# pca10040_sheet4_connectors.net
KiCad netlist of a schematic drawn in Altium Designer
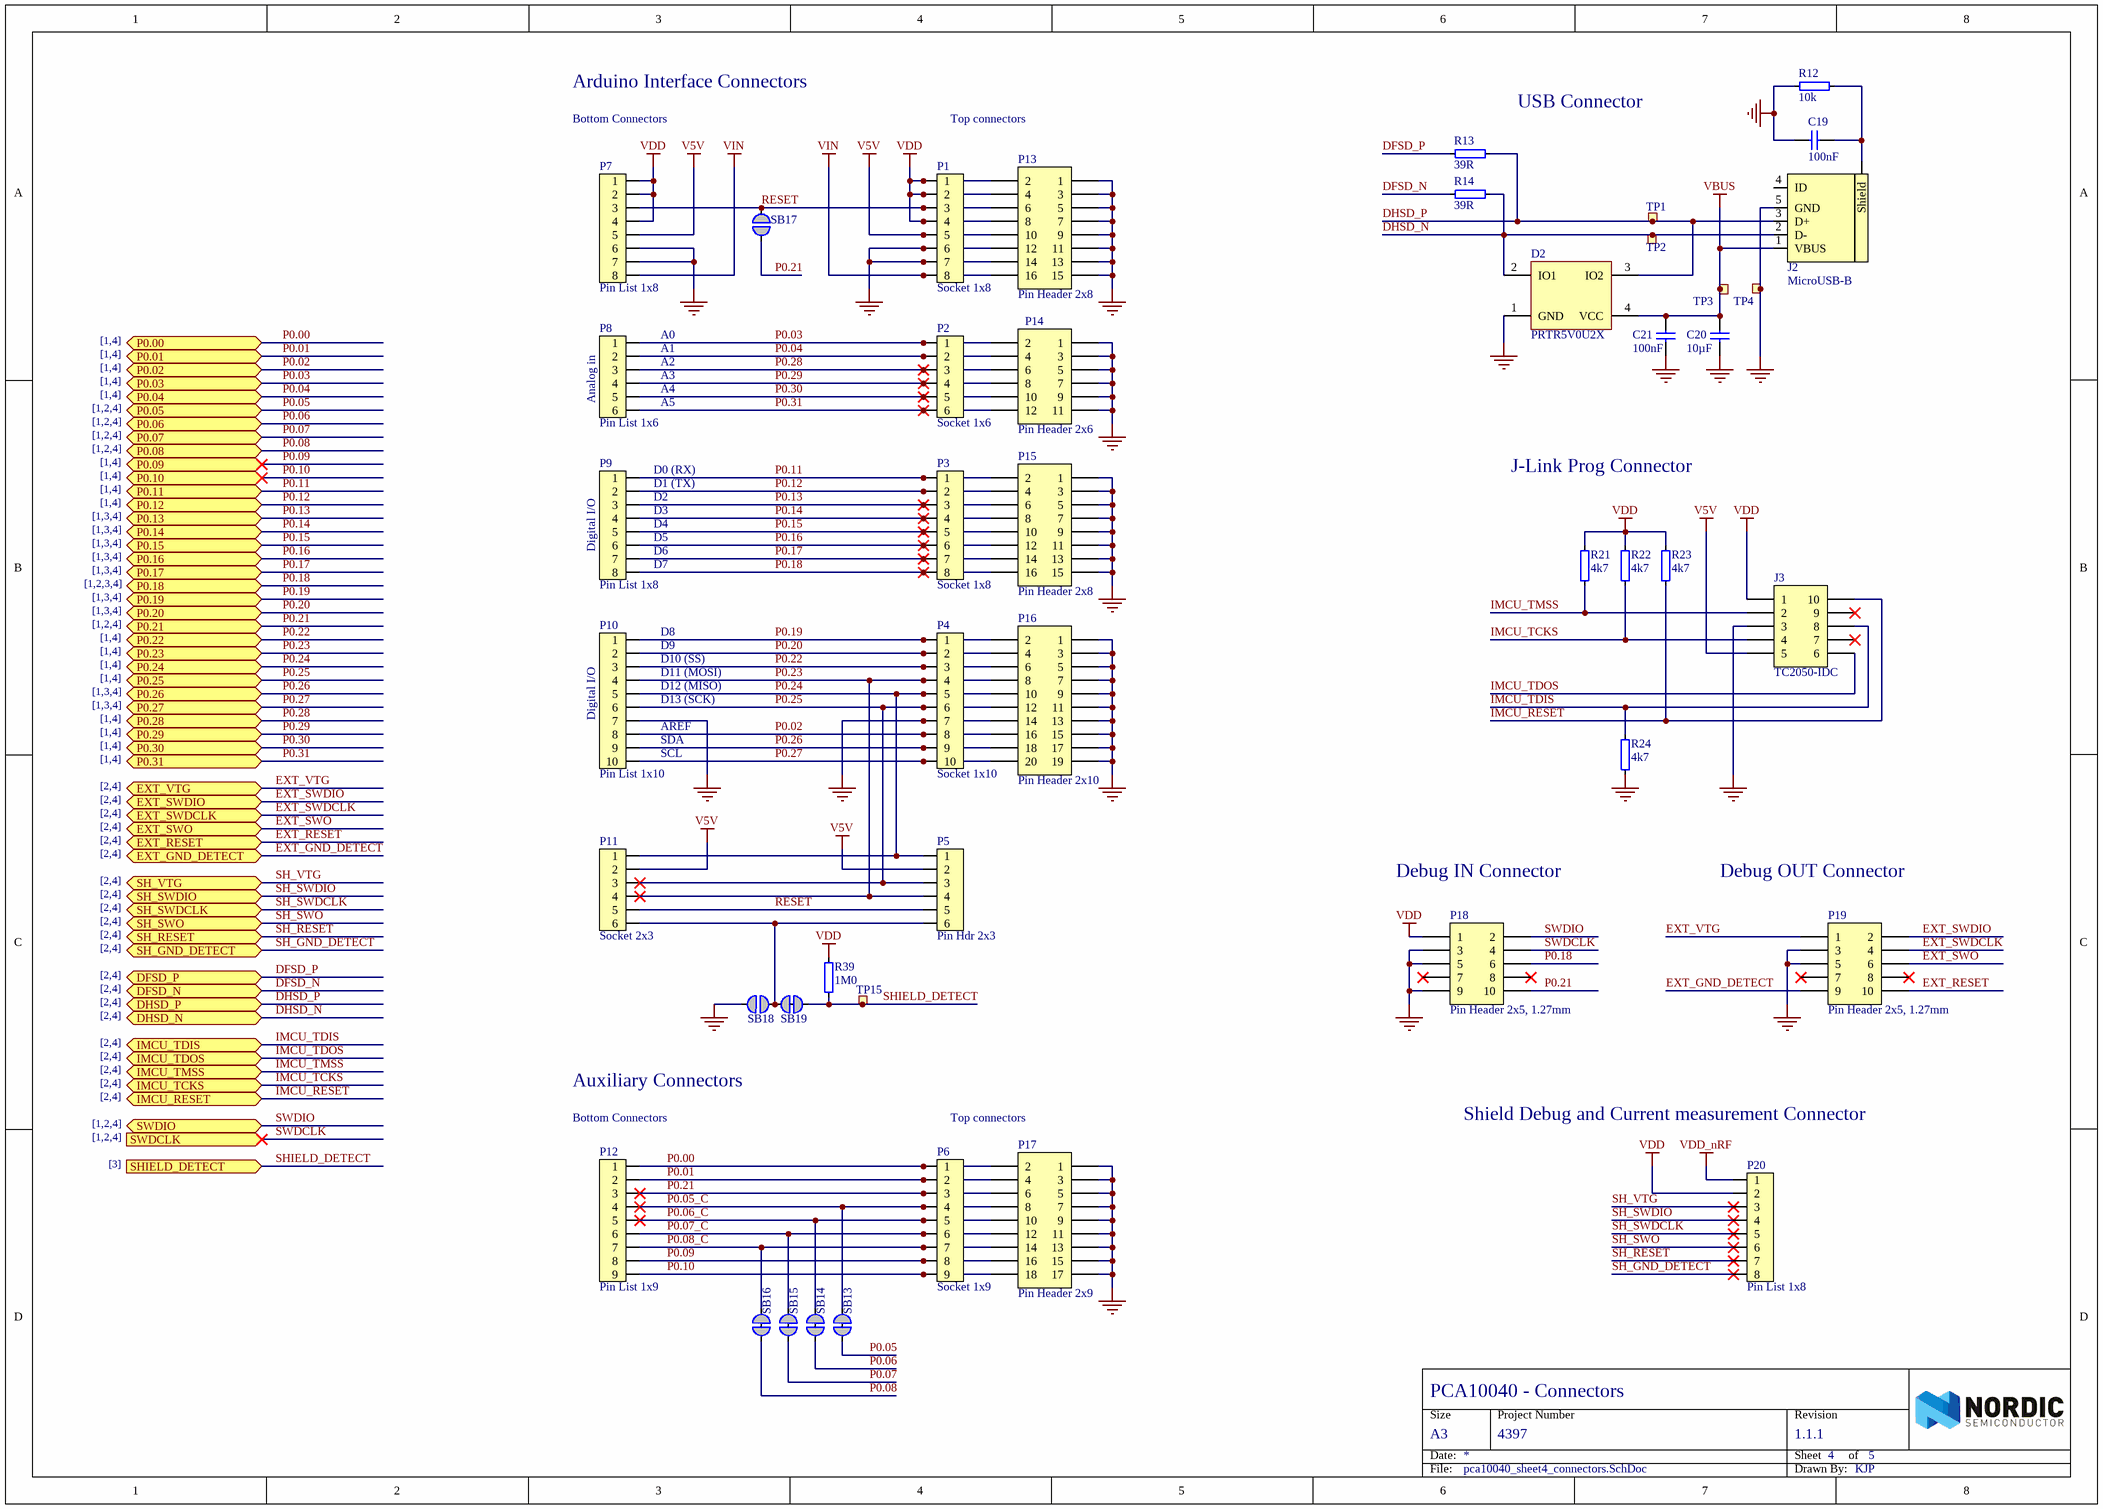
[diagram p0: pca10040_sheet4_connectors.SchDoc]

(export (version "E")
  (design (tool "Eeschema 10.0.6"))
  (components
    (comp (ref "C19")
      (value "100nF")
      (footprint "CAPC1005X04L")
      (description "Capacitor, X7R, ±10%")
      (fields (field (name "PART NUMBER") "C0402-100n") (field (name "PUBLISHER") "Nordic Semiconductor"))
      (libsource (lib "Nordic Passive DB") (part "CAP"))
    )
    (comp (ref "C20")
      (value "10µF")
      (footprint "CAPC1608X06L")
      (description "Capacitor, X5R, ±20%")
      (fields (field (name "PART NUMBER") "C0603-10µ") (field (name "PUBLISHER") "Nordic Semiconductor"))
      (libsource (lib "Nordic Passive DB") (part "CAP"))
    )
    (comp (ref "C21")
      (value "100nF")
      (footprint "CAPC1005X04L")
      (description "Capacitor, X7R, ±10%")
      (fields (field (name "PART NUMBER") "C0402-100n") (field (name "PUBLISHER") "Nordic Semiconductor"))
      (libsource (lib "Nordic Passive DB") (part "CAP"))
    )
    (comp (ref "D2")
      (value "PRTR5V0U2X")
      (footprint "SOT190P230X110-4L")
      (description "Ultra low capacitance double rail-to-rail ESD protection diode")
      (fields
        (field (name "MANUFACTURER") "NXP")
        (field (name "2ND SOURCE PART NUMBER") "152-4157")
        (field (name "PUBLISHER") "Nordic Semiconductor")
      )
      (libsource (lib "Nordic Discrete DB") (part "PRTR5V0U2X"))
    )
    (comp (ref "J2")
      (value "MicroUSB-B")
      (footprint "USB-Micro-B-RA-SMD-PiP")
      (description "MicroUSB-B-SMT")
      (fields
        (field (name "PART NUMBER") "USB-Micro-B-RA-SMD-PiP")
        (field (name "MANUFACTURER") "Allen Creations Corp.")
        (field (name "PUBLISHER") "Nordic Semiconductor")
      )
      (libsource (lib "Nordic Passive DB") (part "MiniUSB-AB-SMT"))
    )
    (comp (ref "J3")
      (value "TC2050-IDC")
      (footprint "TC2050-IDC-NLFP")
      (description "CBL PLUG-OF-NAILS 10-PIN")
      (fields
        (field (name "PART NUMBER") "TC2050-IDC-NLFP")
        (field (name "MANUFACTURER") "Tag-Connect LLC")
        (field (name "PUBLISHER") "Nordic Semiconductor")
      )
      (libsource (lib "Nordic Passive DB") (part "CONN-2x5_var2"))
    )
    (comp (ref "P1")
      (value "Socket 1x8")
      (footprint "SOCKET_1x8_SMD")
      (description "Socket 1x8, 2.54mm (100mil), SMD")
      (fields
        (field (name "PART NUMBER") "Socket 1x8 SMD")
        (field (name "MANUFACTURER") "WCON")
        (field (name "PUBLISHER") "Nordic Semiconductor")
      )
      (libsource (lib "Nordic Passive DB") (part "CONN-8"))
    )
    (comp (ref "P2")
      (value "Socket 1x6")
      (footprint "SOCKET_1x6_SMD")
      (description "Socket 1x6, 2.54mm (100mil), SMD")
      (fields
        (field (name "PART NUMBER") "Socket 1x6 SMD")
        (field (name "MANUFACTURER") "WCON")
        (field (name "PUBLISHER") "Nordic Semiconductor")
      )
      (libsource (lib "Nordic Passive DB") (part "CONN-6"))
    )
    (comp (ref "P3")
      (value "Socket 1x8")
      (footprint "SOCKET_1x8_SMD")
      (description "Socket 1x8, 2.54mm (100mil), SMD")
      (fields
        (field (name "PART NUMBER") "Socket 1x8 SMD")
        (field (name "MANUFACTURER") "WCON")
        (field (name "PUBLISHER") "Nordic Semiconductor")
      )
      (libsource (lib "Nordic Passive DB") (part "CONN-8"))
    )
    (comp (ref "P4")
      (value "Socket 1x10")
      (footprint "SOCKET_1x10_SMD")
      (description "Socket 1x10, 2.54mm (100mil), SMD")
      (fields
        (field (name "PART NUMBER") "Socket 1x10 SMD")
        (field (name "MANUFACTURER") "WCON")
        (field (name "PUBLISHER") "Nordic Semiconductor")
      )
      (libsource (lib "") (part "CONN-10_1"))
    )
    (comp (ref "P5")
      (value "Pin Hdr 2x3")
      (footprint "HDR_2x3-SMD")
      (description "Pin Header 2x3, 2.54mm (100mil) SMD")
      (fields
        (field (name "PART NUMBER") "Pin Header 2x3 SMD")
        (field (name "MANUFACTURER") "WCON")
        (field (name "PUBLISHER") "Nordic Semiconductor")
      )
      (libsource (lib "Nordic Passive DB") (part "CONN-6"))
    )
    (comp (ref "P6")
      (value "Socket 1x9")
      (footprint "SOCKET_1x9_SMD")
      (description "Socket 1x9, 2.54mm (100mil), SMD")
      (fields
        (field (name "PART NUMBER") "Socket 1x9 SMD")
        (field (name "MANUFACTURER") "WCON")
        (field (name "PUBLISHER") "Nordic Semiconductor")
      )
      (libsource (lib "Nordic Passive DB") (part "CONN-9"))
    )
    (comp (ref "P7")
      (value "Pin List 1x8")
      (footprint "LIST_1x8_SMD")
      (description "Pin List 1x8, 2.54mm (100mil), SMD")
      (fields
        (field (name "PART NUMBER") "Pin List 1x8 SMD")
        (field (name "PUBLISHER") "Nordic Semiconductor")
      )
      (libsource (lib "") (part "CONN-8_1"))
    )
    (comp (ref "P8")
      (value "Pin List 1x6")
      (footprint "LIST_1x6_SMD")
      (description "Pin List 1x6, 2.54mm (100mil), SMD")
      (fields
        (field (name "PART NUMBER") "Pin List 1x6 SMD")
        (field (name "PUBLISHER") "Nordic Semiconductor")
      )
      (libsource (lib "") (part "CONN-6_1"))
    )
    (comp (ref "P9")
      (value "Pin List 1x8")
      (footprint "LIST_1x8_SMD")
      (description "Pin List 1x8, 2.54mm (100mil), SMD")
      (fields
        (field (name "PART NUMBER") "Pin List 1x8 SMD")
        (field (name "PUBLISHER") "Nordic Semiconductor")
      )
      (libsource (lib "") (part "CONN-8_1"))
    )
    (comp (ref "P10")
      (value "Pin List 1x10")
      (footprint "LIST_1x10_SMD")
      (description "Pin List 1x10, 2.54mm (100mil), SMD")
      (fields
        (field (name "PART NUMBER") "Pin List 1x10 SMD")
        (field (name "PUBLISHER") "Nordic Semiconductor")
      )
      (libsource (lib "Nordic Passive DB") (part "CONN-10"))
    )
    (comp (ref "P11")
      (value "Socket 2x3")
      (footprint "SOCKET_2x3_SMD-2.54mm-bottom")
      (description "Socket 2x3, 2.54mm (100mil), SMD")
      (fields
        (field (name "PART NUMBER") "Socket 2x3 SMD Bottom")
        (field (name "MANUFACTURER") "Samtec")
        (field (name "PUBLISHER") "Nordic Semiconductor")
      )
      (libsource (lib "") (part "CONN-6_1"))
    )
    (comp (ref "P12")
      (value "Pin List 1x9")
      (footprint "LIST_1x9_SMD")
      (description "Pin List 1x9, 2.54mm (100mil), SMD")
      (fields
        (field (name "PART NUMBER") "Pin List 1x9 SMD")
        (field (name "PUBLISHER") "Nordic Semiconductor")
      )
      (libsource (lib "") (part "CONN-9_1"))
    )
    (comp (ref "P13")
      (value "Pin Header 2x8")
      (footprint "HDR_2x8")
      (description "Pin Header 2x8, 2.54mm (100mil)")
      (fields (field (name "PUBLISHER") "Nordic Semiconductor"))
      (libsource (lib "Nordic Passive DB") (part "CONN-2x8"))
    )
    (comp (ref "P14")
      (value "Pin Header 2x6")
      (footprint "HDR_2x6")
      (description "Pin Header 2x6, 2.54mm (100mil)")
      (fields (field (name "PUBLISHER") "Nordic Semiconductor"))
      (libsource (lib "Nordic Passive DB") (part "CONN-2x6"))
    )
    (comp (ref "P15")
      (value "Pin Header 2x8")
      (footprint "HDR_2x8")
      (description "Pin Header 2x8, 2.54mm (100mil)")
      (fields (field (name "PUBLISHER") "Nordic Semiconductor"))
      (libsource (lib "Nordic Passive DB") (part "CONN-2x8"))
    )
    (comp (ref "P16")
      (value "Pin Header 2x10")
      (footprint "HDR_2x10")
      (description "Pin Header 2x10, 2.54mm (100mil)")
      (fields (field (name "PUBLISHER") "Nordic Semiconductor"))
      (libsource (lib "Nordic Passive DB") (part "CONN-2x10"))
    )
    (comp (ref "P17")
      (value "Pin Header 2x9")
      (footprint "HDR_2x9")
      (description "Pin Header 2x9, 2.54mm (100mil)")
      (fields (field (name "PUBLISHER") "Nordic Semiconductor"))
      (libsource (lib "Nordic Passive DB") (part "CONN-2x9"))
    )
    (comp (ref "P18")
      (value "Pin Header 2x5, 1.27mm")
      (footprint "HDR_2x5-SMD-1.27mm-K")
      (description "Pin Header 2x5, 1.27mm (50mil), SMD, Keying Shroud")
      (fields
        (field (name "PART NUMBER") "Pin Header 2x5 SMD, 1.27mm, KS")
        (field (name "MANUFACTURER") "WCON")
        (field (name "PUBLISHER") "Nordic Semiconductor")
      )
      (libsource (lib "Nordic Passive DB") (part "CONN-2x5"))
    )
    (comp (ref "P19")
      (value "Pin Header 2x5, 1.27mm")
      (footprint "HDR_2x5-SMD-1.27mm-K")
      (description "Pin Header 2x5, 1.27mm (50mil), SMD, Keying Shroud")
      (fields
        (field (name "PART NUMBER") "Pin Header 2x5 SMD, 1.27mm, KS")
        (field (name "MANUFACTURER") "WCON")
        (field (name "PUBLISHER") "Nordic Semiconductor")
      )
      (libsource (lib "Nordic Passive DB") (part "CONN-2x5"))
    )
    (comp (ref "P20")
      (value "Pin List 1x8")
      (footprint "LIST_1x8_SMD")
      (description "Pin List 1x8, 2.54mm (100mil), SMD")
      (fields
        (field (name "PART NUMBER") "Pin List 1x8 SMD")
        (field (name "MANUFACTURER") "WCON")
        (field (name "PUBLISHER") "Nordic Semiconductor")
      )
      (libsource (lib "Nordic Passive DB") (part "CONN-8"))
    )
    (comp (ref "R12")
      (value "10k")
      (footprint "RESC1005X04L")
      (description "Resistor, ±1%, 0.063W")
      (fields (field (name "PART NUMBER") "R0402-10k") (field (name "PUBLISHER") "Nordic Semiconductor"))
      (libsource (lib "Nordic Passive DB") (part "RES_1"))
    )
    (comp (ref "R13")
      (value "39R")
      (footprint "RESC1005X04L")
      (description "Resistor, ±1%, 0.063W")
      (fields (field (name "PART NUMBER") "R0402-39R") (field (name "PUBLISHER") "Nordic Semiconductor"))
      (libsource (lib "Nordic Passive DB") (part "RES_1"))
    )
    (comp (ref "R14")
      (value "39R")
      (footprint "RESC1005X04L")
      (description "Resistor, ±1%, 0.063W")
      (fields (field (name "PART NUMBER") "R0402-39R") (field (name "PUBLISHER") "Nordic Semiconductor"))
      (libsource (lib "Nordic Passive DB") (part "RES_1"))
    )
    (comp (ref "R21")
      (value "4k7")
      (footprint "RESC1005X04L")
      (description "Resistor, ±1%, 0.063W")
      (fields (field (name "PART NUMBER") "R0402-4k7") (field (name "PUBLISHER") "Nordic Semiconductor"))
      (libsource (lib "Nordic Passive DB") (part "RES_1"))
    )
    (comp (ref "R22")
      (value "4k7")
      (footprint "RESC1005X04L")
      (description "Resistor, ±1%, 0.063W")
      (fields (field (name "PART NUMBER") "R0402-4k7") (field (name "PUBLISHER") "Nordic Semiconductor"))
      (libsource (lib "Nordic Passive DB") (part "RES_1"))
    )
    (comp (ref "R23")
      (value "4k7")
      (footprint "RESC1005X04L")
      (description "Resistor, ±1%, 0.063W")
      (fields (field (name "PART NUMBER") "R0402-4k7") (field (name "PUBLISHER") "Nordic Semiconductor"))
      (libsource (lib "Nordic Passive DB") (part "RES_1"))
    )
    (comp (ref "R24")
      (value "4k7")
      (footprint "RESC1005X04L")
      (description "Resistor, ±1%, 0.063W")
      (fields (field (name "PART NUMBER") "R0402-4k7") (field (name "PUBLISHER") "Nordic Semiconductor"))
      (libsource (lib "Nordic Passive DB") (part "RES_1"))
    )
    (comp (ref "R39")
      (value "1M0")
      (footprint "RESC1005X04L")
      (description "Resistor, ±1%, 0.063W")
      (fields (field (name "PART NUMBER") "R0402-1M0") (field (name "PUBLISHER") "Nordic Semiconductor"))
      (libsource (lib "Nordic Passive DB") (part "RES_1"))
    )
    (comp (ref "SB13")
      (value "Solderbridge")
      (footprint "Solderbridge_Shorted")
      (description "Shorted Solderbridge")
      (fields
        (field (name "PART NUMBER") "Solderbridge Shorted")
        (field (name "PUBLISHER") "Nordic Semiconductor")
      )
      (libsource (lib "Nordic Passive DB") (part "SOLDERBRIDGE_SHORTED"))
    )
    (comp (ref "SB14")
      (value "Solderbridge")
      (footprint "Solderbridge_Shorted")
      (description "Shorted Solderbridge")
      (fields
        (field (name "PART NUMBER") "Solderbridge Shorted")
        (field (name "PUBLISHER") "Nordic Semiconductor")
      )
      (libsource (lib "Nordic Passive DB") (part "SOLDERBRIDGE_SHORTED"))
    )
    (comp (ref "SB15")
      (value "Solderbridge")
      (footprint "Solderbridge_Shorted")
      (description "Shorted Solderbridge")
      (fields
        (field (name "PART NUMBER") "Solderbridge Shorted")
        (field (name "PUBLISHER") "Nordic Semiconductor")
      )
      (libsource (lib "Nordic Passive DB") (part "SOLDERBRIDGE_SHORTED"))
    )
    (comp (ref "SB16")
      (value "Solderbridge")
      (footprint "Solderbridge_Shorted")
      (description "Shorted Solderbridge")
      (fields
        (field (name "PART NUMBER") "Solderbridge Shorted")
        (field (name "PUBLISHER") "Nordic Semiconductor")
      )
      (libsource (lib "Nordic Passive DB") (part "SOLDERBRIDGE_SHORTED"))
    )
    (comp (ref "SB17")
      (value "Solderbridge")
      (footprint "Solderbridge")
      (fields (field (name "PUBLISHER") "Nordic Semiconductor"))
      (libsource (lib "Nordic Passive DB") (part "SOLDERBRIDGE"))
    )
    (comp (ref "SB18")
      (value "Solderbridge")
      (footprint "Solderbridge")
      (fields (field (name "PUBLISHER") "Nordic Semiconductor"))
      (libsource (lib "Nordic Passive DB") (part "SOLDERBRIDGE"))
    )
    (comp (ref "SB19")
      (value "Solderbridge")
      (footprint "Solderbridge_Shorted")
      (description "Shorted Solderbridge")
      (fields
        (field (name "PART NUMBER") "Solderbridge Shorted")
        (field (name "PUBLISHER") "Nordic Semiconductor")
      )
      (libsource (lib "Nordic Passive DB") (part "SOLDERBRIDGE_SHORTED"))
    )
    (comp (ref "TP1")
      (value "Ø1.0mm,SMD")
      (footprint "TP_SMD_Ø1.0mm")
      (description "1.0mm circular SMD testpad")
      (fields
        (field (name "PART NUMBER") "TP_SMD_Ø1.0MM")
        (field (name "MANUFACTURER") "Nordic Semiconductor")
        (field (name "PUBLISHER") "Nordic Semiconductor")
      )
      (libsource (lib "Nordic Passive DB") (part "TESTPAD"))
    )
    (comp (ref "TP2")
      (value "Ø1.0mm,SMD")
      (footprint "TP_SMD_Ø1.0mm")
      (description "1.0mm circular SMD testpad")
      (fields
        (field (name "PART NUMBER") "TP_SMD_Ø1.0MM")
        (field (name "MANUFACTURER") "Nordic Semiconductor")
        (field (name "PUBLISHER") "Nordic Semiconductor")
      )
      (libsource (lib "") (part "TESTPAD_1"))
    )
    (comp (ref "TP3")
      (value "Ø1.0mm,SMD")
      (footprint "TP_SMD_Ø1.0mm")
      (description "1.0mm circular SMD testpad")
      (fields
        (field (name "PART NUMBER") "TP_SMD_Ø1.0MM")
        (field (name "MANUFACTURER") "Nordic Semiconductor")
        (field (name "PUBLISHER") "Nordic Semiconductor")
      )
      (libsource (lib "") (part "TESTPAD_2"))
    )
    (comp (ref "TP4")
      (value "Ø1.0mm,SMD")
      (footprint "TP_SMD_Ø1.0mm")
      (description "1.0mm circular SMD testpad")
      (fields
        (field (name "PART NUMBER") "TP_SMD_Ø1.0MM")
        (field (name "MANUFACTURER") "Nordic Semiconductor")
        (field (name "PUBLISHER") "Nordic Semiconductor")
      )
      (libsource (lib "") (part "TESTPAD_3"))
    )
    (comp (ref "TP15")
      (value "Ø1.0mm,SMD")
      (footprint "TP_SMD_Ø1.0mm")
      (description "1.0mm circular SMD testpad")
      (fields
        (field (name "PART NUMBER") "TP_SMD_Ø1.0MM")
        (field (name "MANUFACTURER") "Nordic Semiconductor")
        (field (name "PUBLISHER") "Nordic Semiconductor")
      )
      (libsource (lib "Nordic Passive DB") (part "TESTPAD"))
    )
  )
  (nets
    (net (code "1") (name "/DFSD_N") (class "Default")
      (node (ref "R14") (pin "1") (pinfunction "1_1") (pintype "passive"))
    )
    (net (code "2") (name "/DFSD_P") (class "Default")
      (node (ref "R13") (pin "1") (pinfunction "1_1") (pintype "passive"))
    )
    (net (code "3") (name "/DHSD_N") (class "Default")
      (node (ref "D2") (pin "2") (pinfunction "IO1_2") (pintype "passive"))
      (node (ref "J2") (pin "2") (pinfunction "D-_2") (pintype "passive"))
      (node (ref "R14") (pin "2") (pinfunction "2_2") (pintype "passive"))
      (node (ref "TP2") (pin "1") (pinfunction "1_1") (pintype "passive"))
    )
    (net (code "4") (name "/DHSD_P") (class "Default")
      (node (ref "D2") (pin "3") (pinfunction "IO2_3") (pintype "passive"))
      (node (ref "J2") (pin "3") (pinfunction "D+_3") (pintype "passive"))
      (node (ref "R13") (pin "2") (pinfunction "2_2") (pintype "passive"))
      (node (ref "TP1") (pin "1") (pinfunction "1_1") (pintype "passive"))
    )
    (net (code "5") (name "/EXT_GND_DETECT") (class "Default")
      (node (ref "P19") (pin "9") (pinfunction "9_9") (pintype "passive"))
    )
    (net (code "6") (name "/EXT_RESET") (class "Default")
      (node (ref "P19") (pin "10") (pinfunction "10_10") (pintype "passive"))
    )
    (net (code "7") (name "/EXT_SWDCLK") (class "Default")
      (node (ref "P19") (pin "4") (pinfunction "4_4") (pintype "passive"))
    )
    (net (code "8") (name "/EXT_SWDIO") (class "Default")
      (node (ref "P19") (pin "2") (pinfunction "2_2") (pintype "passive"))
    )
    (net (code "9") (name "/EXT_SWO") (class "Default")
      (node (ref "P19") (pin "6") (pinfunction "6_6") (pintype "passive"))
    )
    (net (code "10") (name "/EXT_VTG") (class "Default")
      (node (ref "P19") (pin "1") (pinfunction "1_1") (pintype "passive"))
    )
    (net (code "11") (name "/IMCU_RESET") (class "Default")
      (node (ref "J3") (pin "10") (pinfunction "10_10") (pintype "passive"))
      (node (ref "R23") (pin "1") (pinfunction "1_1") (pintype "passive"))
    )
    (net (code "12") (name "/IMCU_TCKS") (class "Default")
      (node (ref "J3") (pin "4") (pinfunction "4_4") (pintype "passive"))
      (node (ref "R22") (pin "1") (pinfunction "1_1") (pintype "passive"))
    )
    (net (code "13") (name "/IMCU_TDIS") (class "Default")
      (node (ref "J3") (pin "8") (pinfunction "8_8") (pintype "passive"))
      (node (ref "R24") (pin "1") (pinfunction "1_1") (pintype "passive"))
    )
    (net (code "14") (name "/IMCU_TDOS") (class "Default")
      (node (ref "J3") (pin "6") (pinfunction "6_6") (pintype "passive"))
    )
    (net (code "15") (name "/IMCU_TMSS") (class "Default")
      (node (ref "J3") (pin "2") (pinfunction "2_2") (pintype "passive"))
      (node (ref "R21") (pin "1") (pinfunction "1_1") (pintype "passive"))
    )
    (net (code "16") (name "/P0.00") (class "Default")
      (node (ref "P12") (pin "1") (pinfunction "1_1") (pintype "passive"))
      (node (ref "P17") (pin "2") (pinfunction "2_2") (pintype "passive"))
      (node (ref "P6") (pin "1") (pinfunction "1_1") (pintype "passive"))
    )
    (net (code "17") (name "/P0.01") (class "Default")
      (node (ref "P12") (pin "2") (pinfunction "2_2") (pintype "passive"))
      (node (ref "P17") (pin "4") (pinfunction "4_4") (pintype "passive"))
      (node (ref "P6") (pin "2") (pinfunction "2_2") (pintype "passive"))
    )
    (net (code "18") (name "/P0.02") (class "Default")
      (node (ref "P10") (pin "8") (pinfunction "8_8") (pintype "passive"))
      (node (ref "P16") (pin "16") (pinfunction "16_16") (pintype "passive"))
      (node (ref "P4") (pin "8") (pinfunction "8_8") (pintype "passive"))
    )
    (net (code "19") (name "/P0.03") (class "Default")
      (node (ref "P14") (pin "2") (pinfunction "2_2") (pintype "passive"))
      (node (ref "P2") (pin "1") (pinfunction "1_1") (pintype "passive"))
      (node (ref "P8") (pin "1") (pinfunction "1_1") (pintype "passive"))
    )
    (net (code "20") (name "/P0.04") (class "Default")
      (node (ref "P14") (pin "4") (pinfunction "4_4") (pintype "passive"))
      (node (ref "P2") (pin "2") (pinfunction "2_2") (pintype "passive"))
      (node (ref "P8") (pin "2") (pinfunction "2_2") (pintype "passive"))
    )
    (net (code "21") (name "/P0.05") (class "Default")
      (node (ref "SB13") (pin "2") (pinfunction "1_2") (pintype "passive"))
    )
    (net (code "22") (name "/P0.05_C") (class "Default")
      (node (ref "P12") (pin "4") (pinfunction "4_4") (pintype "power_in"))
      (node (ref "P17") (pin "8") (pinfunction "8_8") (pintype "passive"))
      (node (ref "P6") (pin "4") (pinfunction "4_4") (pintype "power_in"))
      (node (ref "SB13") (pin "1") (pinfunction "0_1") (pintype "passive"))
    )
    (net (code "23") (name "/P0.06") (class "Default")
      (node (ref "SB14") (pin "2") (pinfunction "1_2") (pintype "passive"))
    )
    (net (code "24") (name "/P0.06_C") (class "Default")
      (node (ref "P12") (pin "5") (pinfunction "5_5") (pintype "power_in"))
      (node (ref "P17") (pin "10") (pinfunction "10_10") (pintype "passive"))
      (node (ref "P6") (pin "5") (pinfunction "5_5") (pintype "power_in"))
      (node (ref "SB14") (pin "1") (pinfunction "0_1") (pintype "passive"))
    )
    (net (code "25") (name "/P0.07") (class "Default")
      (node (ref "SB15") (pin "2") (pinfunction "1_2") (pintype "passive"))
    )
    (net (code "26") (name "/P0.07_C") (class "Default")
      (node (ref "P12") (pin "6") (pinfunction "6_6") (pintype "power_in"))
      (node (ref "P17") (pin "12") (pinfunction "12_12") (pintype "passive"))
      (node (ref "P6") (pin "6") (pinfunction "6_6") (pintype "power_in"))
      (node (ref "SB15") (pin "1") (pinfunction "0_1") (pintype "passive"))
    )
    (net (code "27") (name "/P0.08") (class "Default")
      (node (ref "SB16") (pin "2") (pinfunction "1_2") (pintype "passive"))
    )
    (net (code "28") (name "/P0.08_C") (class "Default")
      (node (ref "P12") (pin "7") (pinfunction "7_7") (pintype "power_in"))
      (node (ref "P17") (pin "14") (pinfunction "14_14") (pintype "passive"))
      (node (ref "P6") (pin "7") (pinfunction "7_7") (pintype "power_in"))
      (node (ref "SB16") (pin "1") (pinfunction "0_1") (pintype "passive"))
    )
    (net (code "29") (name "/P0.09") (class "Default")
      (node (ref "P12") (pin "8") (pinfunction "8_8") (pintype "power_in"))
      (node (ref "P17") (pin "16") (pinfunction "16_16") (pintype "passive"))
      (node (ref "P6") (pin "8") (pinfunction "8_8") (pintype "power_in"))
    )
    (net (code "30") (name "/P0.10") (class "Default")
      (node (ref "P12") (pin "9") (pinfunction "9_9") (pintype "power_in"))
      (node (ref "P17") (pin "18") (pinfunction "18_18") (pintype "passive"))
      (node (ref "P6") (pin "9") (pinfunction "9_9") (pintype "power_in"))
    )
    (net (code "31") (name "/P0.11") (class "Default")
      (node (ref "P15") (pin "2") (pinfunction "2_2") (pintype "passive"))
      (node (ref "P3") (pin "1") (pinfunction "1_1") (pintype "passive"))
      (node (ref "P9") (pin "1") (pinfunction "1_1") (pintype "passive"))
    )
    (net (code "32") (name "/P0.12") (class "Default")
      (node (ref "P15") (pin "4") (pinfunction "4_4") (pintype "passive"))
      (node (ref "P3") (pin "2") (pinfunction "2_2") (pintype "passive"))
      (node (ref "P9") (pin "2") (pinfunction "2_2") (pintype "passive"))
    )
    (net (code "33") (name "/P0.13") (class "Default")
      (node (ref "P15") (pin "6") (pinfunction "6_6") (pintype "passive"))
      (node (ref "P3") (pin "3") (pinfunction "3_3") (pintype "passive"))
      (node (ref "P9") (pin "3") (pinfunction "3_3") (pintype "power_in"))
    )
    (net (code "34") (name "/P0.14") (class "Default")
      (node (ref "P15") (pin "8") (pinfunction "8_8") (pintype "passive"))
      (node (ref "P3") (pin "4") (pinfunction "4_4") (pintype "passive"))
      (node (ref "P9") (pin "4") (pinfunction "4_4") (pintype "power_in"))
    )
    (net (code "35") (name "/P0.15") (class "Default")
      (node (ref "P15") (pin "10") (pinfunction "10_10") (pintype "passive"))
      (node (ref "P3") (pin "5") (pinfunction "5_5") (pintype "passive"))
      (node (ref "P9") (pin "5") (pinfunction "5_5") (pintype "power_in"))
    )
    (net (code "36") (name "/P0.16") (class "Default")
      (node (ref "P15") (pin "12") (pinfunction "12_12") (pintype "passive"))
      (node (ref "P3") (pin "6") (pinfunction "6_6") (pintype "passive"))
      (node (ref "P9") (pin "6") (pinfunction "6_6") (pintype "power_in"))
    )
    (net (code "37") (name "/P0.17") (class "Default")
      (node (ref "P15") (pin "14") (pinfunction "14_14") (pintype "passive"))
      (node (ref "P3") (pin "7") (pinfunction "7_7") (pintype "passive"))
      (node (ref "P9") (pin "7") (pinfunction "7_7") (pintype "power_in"))
    )
    (net (code "38") (name "/P0.18") (class "Default")
      (node (ref "P15") (pin "16") (pinfunction "16_16") (pintype "passive"))
      (node (ref "P18") (pin "6") (pinfunction "6_6") (pintype "passive"))
      (node (ref "P3") (pin "8") (pinfunction "8_8") (pintype "passive"))
      (node (ref "P9") (pin "8") (pinfunction "8_8") (pintype "power_in"))
    )
    (net (code "39") (name "/P0.19") (class "Default")
      (node (ref "P10") (pin "1") (pinfunction "1_1") (pintype "passive"))
      (node (ref "P16") (pin "2") (pinfunction "2_2") (pintype "passive"))
      (node (ref "P4") (pin "1") (pinfunction "1_1") (pintype "passive"))
    )
    (net (code "40") (name "/P0.20") (class "Default")
      (node (ref "P10") (pin "2") (pinfunction "2_2") (pintype "passive"))
      (node (ref "P16") (pin "4") (pinfunction "4_4") (pintype "passive"))
      (node (ref "P4") (pin "2") (pinfunction "2_2") (pintype "passive"))
    )
    (net (code "41") (name "/P0.21") (class "Default")
      (node (ref "P12") (pin "3") (pinfunction "3_3") (pintype "power_in"))
      (node (ref "P17") (pin "6") (pinfunction "6_6") (pintype "passive"))
      (node (ref "P18") (pin "10") (pinfunction "10_10") (pintype "passive"))
      (node (ref "P6") (pin "3") (pinfunction "3_3") (pintype "power_in"))
      (node (ref "SB17") (pin "2") (pinfunction "1_2") (pintype "passive"))
    )
    (net (code "42") (name "/P0.22") (class "Default")
      (node (ref "P10") (pin "3") (pinfunction "3_3") (pintype "passive"))
      (node (ref "P16") (pin "6") (pinfunction "6_6") (pintype "passive"))
      (node (ref "P4") (pin "3") (pinfunction "3_3") (pintype "passive"))
    )
    (net (code "43") (name "/P0.23") (class "Default")
      (node (ref "P10") (pin "4") (pinfunction "4_4") (pintype "passive"))
      (node (ref "P11") (pin "4") (pinfunction "4_4") (pintype "power_in"))
      (node (ref "P16") (pin "8") (pinfunction "8_8") (pintype "passive"))
      (node (ref "P4") (pin "4") (pinfunction "4_4") (pintype "passive"))
      (node (ref "P5") (pin "4") (pinfunction "4_4") (pintype "passive"))
    )
    (net (code "44") (name "/P0.24") (class "Default")
      (node (ref "P10") (pin "5") (pinfunction "5_5") (pintype "passive"))
      (node (ref "P11") (pin "1") (pinfunction "1_1") (pintype "passive"))
      (node (ref "P16") (pin "10") (pinfunction "10_10") (pintype "passive"))
      (node (ref "P4") (pin "5") (pinfunction "5_5") (pintype "passive"))
      (node (ref "P5") (pin "1") (pinfunction "1_1") (pintype "passive"))
    )
    (net (code "45") (name "/P0.25") (class "Default")
      (node (ref "P10") (pin "6") (pinfunction "6_6") (pintype "passive"))
      (node (ref "P11") (pin "3") (pinfunction "3_3") (pintype "power_in"))
      (node (ref "P16") (pin "12") (pinfunction "12_12") (pintype "passive"))
      (node (ref "P4") (pin "6") (pinfunction "6_6") (pintype "passive"))
      (node (ref "P5") (pin "3") (pinfunction "3_3") (pintype "passive"))
    )
    (net (code "46") (name "/P0.26") (class "Default")
      (node (ref "P10") (pin "9") (pinfunction "9_9") (pintype "passive"))
      (node (ref "P16") (pin "18") (pinfunction "18_18") (pintype "passive"))
      (node (ref "P4") (pin "9") (pinfunction "9_9") (pintype "passive"))
    )
    (net (code "47") (name "/P0.27") (class "Default")
      (node (ref "P10") (pin "10") (pinfunction "10_10") (pintype "passive"))
      (node (ref "P16") (pin "20") (pinfunction "20_20") (pintype "passive"))
      (node (ref "P4") (pin "10") (pinfunction "10_10") (pintype "passive"))
    )
    (net (code "48") (name "/P0.28") (class "Default")
      (node (ref "P14") (pin "6") (pinfunction "6_6") (pintype "passive"))
      (node (ref "P2") (pin "3") (pinfunction "3_3") (pintype "passive"))
      (node (ref "P8") (pin "3") (pinfunction "3_3") (pintype "power_in"))
    )
    (net (code "49") (name "/P0.29") (class "Default")
      (node (ref "P14") (pin "8") (pinfunction "8_8") (pintype "passive"))
      (node (ref "P2") (pin "4") (pinfunction "4_4") (pintype "passive"))
      (node (ref "P8") (pin "4") (pinfunction "4_4") (pintype "power_in"))
    )
    (net (code "50") (name "/P0.30") (class "Default")
      (node (ref "P14") (pin "10") (pinfunction "10_10") (pintype "passive"))
      (node (ref "P2") (pin "5") (pinfunction "5_5") (pintype "passive"))
      (node (ref "P8") (pin "5") (pinfunction "5_5") (pintype "power_in"))
    )
    (net (code "51") (name "/P0.31") (class "Default")
      (node (ref "P14") (pin "12") (pinfunction "12_12") (pintype "passive"))
      (node (ref "P2") (pin "6") (pinfunction "6_6") (pintype "passive"))
      (node (ref "P8") (pin "6") (pinfunction "6_6") (pintype "power_in"))
    )
    (net (code "52") (name "/RESET") (class "Default")
      (node (ref "P1") (pin "3") (pinfunction "3_3") (pintype "passive"))
      (node (ref "P11") (pin "5") (pinfunction "5_5") (pintype "power_in"))
      (node (ref "P13") (pin "6") (pinfunction "6_6") (pintype "passive"))
      (node (ref "P5") (pin "5") (pinfunction "5_5") (pintype "passive"))
      (node (ref "P7") (pin "3") (pinfunction "3_3") (pintype "power_in"))
      (node (ref "SB17") (pin "1") (pinfunction "0_1") (pintype "passive"))
    )
    (net (code "53") (name "/SHIELD_DETECT") (class "Default")
      (node (ref "R39") (pin "1") (pinfunction "1_1") (pintype "passive"))
      (node (ref "SB19") (pin "2") (pinfunction "1_2") (pintype "passive"))
      (node (ref "TP15") (pin "1") (pinfunction "1_1") (pintype "passive"))
    )
    (net (code "54") (name "/SH_GND_DETECT") (class "Default")
      (node (ref "P20") (pin "8") (pinfunction "8_8") (pintype "passive"))
    )
    (net (code "55") (name "/SH_RESET") (class "Default")
      (node (ref "P20") (pin "7") (pinfunction "7_7") (pintype "passive"))
    )
    (net (code "56") (name "/SH_SWDCLK") (class "Default")
      (node (ref "P20") (pin "5") (pinfunction "5_5") (pintype "passive"))
    )
    (net (code "57") (name "/SH_SWDIO") (class "Default")
      (node (ref "P20") (pin "4") (pinfunction "4_4") (pintype "passive"))
    )
    (net (code "58") (name "/SH_SWO") (class "Default")
      (node (ref "P20") (pin "6") (pinfunction "6_6") (pintype "passive"))
    )
    (net (code "59") (name "/SH_VTG") (class "Default")
      (node (ref "P20") (pin "3") (pinfunction "3_3") (pintype "passive"))
    )
    (net (code "60") (name "/SWDCLK") (class "Default")
      (node (ref "P18") (pin "4") (pinfunction "4_4") (pintype "passive+no_connect"))
    )
    (net (code "61") (name "/SWDIO") (class "Default")
      (node (ref "P18") (pin "2") (pinfunction "2_2") (pintype "passive"))
    )
    (net (code "62") (name "GND") (class "Default")
      (node (ref "C19") (pin "1") (pinfunction "1_1") (pintype "passive"))
      (node (ref "C20") (pin "1") (pinfunction "1_1") (pintype "passive"))
      (node (ref "C21") (pin "1") (pinfunction "1_1") (pintype "passive"))
      (node (ref "D2") (pin "1") (pinfunction "GND_1") (pintype "passive"))
      (node (ref "J2") (pin "5") (pinfunction "GND_5") (pintype "power_in"))
      (node (ref "J3") (pin "3") (pinfunction "3_3") (pintype "passive"))
      (node (ref "P1") (pin "6") (pinfunction "6_6") (pintype "passive"))
      (node (ref "P1") (pin "7") (pinfunction "7_7") (pintype "passive"))
      (node (ref "P10") (pin "7") (pinfunction "7_7") (pintype "passive"))
      (node (ref "P13") (pin "1") (pinfunction "1_1") (pintype "passive"))
      (node (ref "P13") (pin "11") (pinfunction "11_11") (pintype "passive"))
      (node (ref "P13") (pin "12") (pinfunction "12_12") (pintype "passive"))
      (node (ref "P13") (pin "13") (pinfunction "13_13") (pintype "passive"))
      (node (ref "P13") (pin "14") (pinfunction "14_14") (pintype "passive"))
      (node (ref "P13") (pin "15") (pinfunction "15_15") (pintype "passive"))
      (node (ref "P13") (pin "3") (pinfunction "3_3") (pintype "passive"))
      (node (ref "P13") (pin "5") (pinfunction "5_5") (pintype "passive"))
      (node (ref "P13") (pin "7") (pinfunction "7_7") (pintype "passive"))
      (node (ref "P13") (pin "9") (pinfunction "9_9") (pintype "passive"))
      (node (ref "P14") (pin "1") (pinfunction "1_1") (pintype "passive"))
      (node (ref "P14") (pin "11") (pinfunction "11_11") (pintype "passive"))
      (node (ref "P14") (pin "3") (pinfunction "3_3") (pintype "passive"))
      (node (ref "P14") (pin "5") (pinfunction "5_5") (pintype "passive"))
      (node (ref "P14") (pin "7") (pinfunction "7_7") (pintype "passive"))
      (node (ref "P14") (pin "9") (pinfunction "9_9") (pintype "passive"))
      (node (ref "P15") (pin "1") (pinfunction "1_1") (pintype "passive"))
      (node (ref "P15") (pin "11") (pinfunction "11_11") (pintype "passive"))
      (node (ref "P15") (pin "13") (pinfunction "13_13") (pintype "passive"))
      (node (ref "P15") (pin "15") (pinfunction "15_15") (pintype "passive"))
      (node (ref "P15") (pin "3") (pinfunction "3_3") (pintype "passive"))
      (node (ref "P15") (pin "5") (pinfunction "5_5") (pintype "passive"))
      (node (ref "P15") (pin "7") (pinfunction "7_7") (pintype "passive"))
      (node (ref "P15") (pin "9") (pinfunction "9_9") (pintype "passive"))
      (node (ref "P16") (pin "1") (pinfunction "1_1") (pintype "passive"))
      (node (ref "P16") (pin "11") (pinfunction "11_11") (pintype "passive"))
      (node (ref "P16") (pin "13") (pinfunction "13_13") (pintype "passive"))
      (node (ref "P16") (pin "14") (pinfunction "14_14") (pintype "passive"))
      (node (ref "P16") (pin "15") (pinfunction "15_15") (pintype "passive"))
      (node (ref "P16") (pin "17") (pinfunction "17_17") (pintype "passive"))
      (node (ref "P16") (pin "19") (pinfunction "19_19") (pintype "passive"))
      (node (ref "P16") (pin "3") (pinfunction "3_3") (pintype "passive"))
      (node (ref "P16") (pin "5") (pinfunction "5_5") (pintype "passive"))
      (node (ref "P16") (pin "7") (pinfunction "7_7") (pintype "passive"))
      (node (ref "P16") (pin "9") (pinfunction "9_9") (pintype "passive"))
      (node (ref "P17") (pin "1") (pinfunction "1_1") (pintype "passive"))
      (node (ref "P17") (pin "11") (pinfunction "11_11") (pintype "passive"))
      (node (ref "P17") (pin "13") (pinfunction "13_13") (pintype "passive"))
      (node (ref "P17") (pin "15") (pinfunction "15_15") (pintype "passive"))
      (node (ref "P17") (pin "17") (pinfunction "17_17") (pintype "passive"))
      (node (ref "P17") (pin "3") (pinfunction "3_3") (pintype "passive"))
      (node (ref "P17") (pin "5") (pinfunction "5_5") (pintype "passive"))
      (node (ref "P17") (pin "7") (pinfunction "7_7") (pintype "passive"))
      (node (ref "P17") (pin "9") (pinfunction "9_9") (pintype "passive"))
      (node (ref "P18") (pin "3") (pinfunction "3_3") (pintype "passive"))
      (node (ref "P18") (pin "5") (pinfunction "5_5") (pintype "passive"))
      (node (ref "P18") (pin "9") (pinfunction "9_9") (pintype "passive"))
      (node (ref "P19") (pin "3") (pinfunction "3_3") (pintype "passive"))
      (node (ref "P19") (pin "5") (pinfunction "5_5") (pintype "passive"))
      (node (ref "P4") (pin "7") (pinfunction "7_7") (pintype "passive"))
      (node (ref "P7") (pin "6") (pinfunction "6_6") (pintype "power_in"))
      (node (ref "P7") (pin "7") (pinfunction "7_7") (pintype "power_in"))
      (node (ref "R12") (pin "1") (pinfunction "1_1") (pintype "passive"))
      (node (ref "R24") (pin "2") (pinfunction "2_2") (pintype "passive"))
      (node (ref "SB18") (pin "1") (pinfunction "0_1") (pintype "passive"))
      (node (ref "TP4") (pin "1") (pinfunction "1_1") (pintype "passive"))
    )
    (net (code "63") (name "Net-(J2-Shield)") (class "Default")
      (node (ref "C19") (pin "2") (pinfunction "2_2") (pintype "passive"))
      (node (ref "J2") (pin "6") (pinfunction "Shield_6") (pintype "power_in"))
      (node (ref "R12") (pin "2") (pinfunction "2_2") (pintype "passive"))
    )
    (net (code "64") (name "Net-(SB18-1)") (class "Default")
      (node (ref "P11") (pin "6") (pinfunction "6_6") (pintype "power_in"))
      (node (ref "P5") (pin "6") (pinfunction "6_6") (pintype "passive"))
      (node (ref "SB18") (pin "2") (pinfunction "1_2") (pintype "passive"))
      (node (ref "SB19") (pin "1") (pinfunction "0_1") (pintype "passive"))
    )
    (net (code "65") (name "V5V") (class "Default")
      (node (ref "J3") (pin "5") (pinfunction "5_5") (pintype "passive"))
      (node (ref "P1") (pin "5") (pinfunction "5_5") (pintype "passive"))
      (node (ref "P11") (pin "2") (pinfunction "2_2") (pintype "passive"))
      (node (ref "P13") (pin "10") (pinfunction "10_10") (pintype "passive"))
      (node (ref "P5") (pin "2") (pinfunction "2_2") (pintype "passive"))
      (node (ref "P7") (pin "5") (pinfunction "5_5") (pintype "power_in"))
    )
    (net (code "66") (name "VBUS") (class "Default")
      (node (ref "C20") (pin "2") (pinfunction "2_2") (pintype "passive"))
      (node (ref "C21") (pin "2") (pinfunction "2_2") (pintype "passive"))
      (node (ref "D2") (pin "4") (pinfunction "VCC_4") (pintype "passive"))
      (node (ref "J2") (pin "1") (pinfunction "VBUS_1") (pintype "power_in"))
      (node (ref "TP3") (pin "1") (pinfunction "1_1") (pintype "passive"))
    )
    (net (code "67") (name "VDD") (class "Default")
      (node (ref "J3") (pin "1") (pinfunction "1_1") (pintype "passive"))
      (node (ref "P1") (pin "1") (pinfunction "1_1") (pintype "passive"))
      (node (ref "P1") (pin "2") (pinfunction "2_2") (pintype "passive"))
      (node (ref "P1") (pin "4") (pinfunction "4_4") (pintype "passive"))
      (node (ref "P13") (pin "2") (pinfunction "2_2") (pintype "passive"))
      (node (ref "P13") (pin "4") (pinfunction "4_4") (pintype "passive"))
      (node (ref "P13") (pin "8") (pinfunction "8_8") (pintype "passive"))
      (node (ref "P18") (pin "1") (pinfunction "1_1") (pintype "passive"))
      (node (ref "P20") (pin "2") (pinfunction "2_2") (pintype "passive"))
      (node (ref "P7") (pin "1") (pinfunction "1_1") (pintype "passive"))
      (node (ref "P7") (pin "2") (pinfunction "2_2") (pintype "passive"))
      (node (ref "P7") (pin "4") (pinfunction "4_4") (pintype "power_in"))
      (node (ref "R21") (pin "2") (pinfunction "2_2") (pintype "passive"))
      (node (ref "R22") (pin "2") (pinfunction "2_2") (pintype "passive"))
      (node (ref "R23") (pin "2") (pinfunction "2_2") (pintype "passive"))
      (node (ref "R39") (pin "2") (pinfunction "2_2") (pintype "passive"))
    )
    (net (code "68") (name "VDD_nRF") (class "Default")
      (node (ref "P20") (pin "1") (pinfunction "1_1") (pintype "passive"))
    )
    (net (code "69") (name "VIN") (class "Default")
      (node (ref "P1") (pin "8") (pinfunction "8_8") (pintype "passive"))
      (node (ref "P13") (pin "16") (pinfunction "16_16") (pintype "passive"))
      (node (ref "P7") (pin "8") (pinfunction "8_8") (pintype "power_in"))
    )
    (net (code "70") (name "unconnected-(J2-ID-Pad4)") (class "Default")
      (node (ref "J2") (pin "4") (pinfunction "ID_4") (pintype "passive"))
    )
    (net (code "71") (name "unconnected-(J3-Pad7)") (class "Default")
      (node (ref "J3") (pin "7") (pinfunction "7_7") (pintype "passive+no_connect"))
    )
    (net (code "72") (name "unconnected-(J3-Pad9)") (class "Default")
      (node (ref "J3") (pin "9") (pinfunction "9_9") (pintype "passive+no_connect"))
    )
    (net (code "73") (name "unconnected-(P18-Pad7)") (class "Default")
      (node (ref "P18") (pin "7") (pinfunction "7_7") (pintype "passive+no_connect"))
    )
    (net (code "74") (name "unconnected-(P18-Pad8)") (class "Default")
      (node (ref "P18") (pin "8") (pinfunction "8_8") (pintype "passive+no_connect"))
    )
    (net (code "75") (name "unconnected-(P19-Pad7)") (class "Default")
      (node (ref "P19") (pin "7") (pinfunction "7_7") (pintype "passive+no_connect"))
    )
    (net (code "76") (name "unconnected-(P19-Pad8)") (class "Default")
      (node (ref "P19") (pin "8") (pinfunction "8_8") (pintype "passive+no_connect"))
    )
  )
)
